# HTS221.net
KiCad netlist of a schematic drawn in Altium Designer
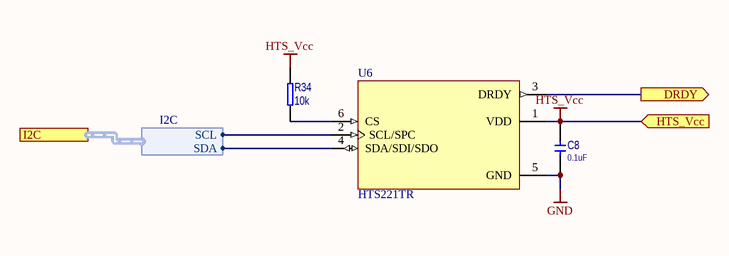
[diagram p0: HTS221.SchDoc]

(export (version "E")
  (design (tool "Eeschema 10.0.6"))
  (components
    (comp (ref "C8")
      (value "0.1uF")
      (footprint "CERCAP 0402")
      (description "Capacitor")
      (fields (field (name "Comment") "CERCAP 0402 0.1uF * X7R"))
      (libsource (lib "!main") (part "!Capacitor"))
    )
    (comp (ref "R34")
      (value "10k")
      (footprint "RES 0402")
      (description "Resistor")
      (fields (field (name "Comment") "RES 0402 10k"))
      (libsource (lib "!main") (part "!Resistor"))
    )
    (comp (ref "U6")
      (value "HTS221TR")
      (footprint "SI_PCBLIB_LGA:LGA6_HTS221")
      (description "Humidity Temperature Sensor 0 ~ 100% RH IÂ²C, SPI Â±4.5% RH 10s Surface Mount")
      (fields (field (name "MF") "STMicroelectronics") (field (name "DIGI-KEY_PART_NUMBER") "497-15382-1-ND"))
      (libsource (lib "SI_LIBSCH_Sensors") (part "HTS221TR"))
    )
  )
  (nets
    (net (code "2") (name "/DRDY") (class "Default")
      (node (ref "U6") (pin "3") (pinfunction "DRDY_3") (pintype "output"))
    )
    (net (code "3") (name "/SCL") (class "Default")
      (node (ref "U6") (pin "2") (pinfunction "SCL/SPC_2") (pintype "input"))
    )
    (net (code "4") (name "/SDA") (class "Default")
      (node (ref "U6") (pin "4") (pinfunction "SDA/SDI/SDO_4") (pintype "bidirectional"))
    )
    (net (code "6") (name "GND") (class "Default")
      (node (ref "C8") (pin "1") (pintype "passive"))
      (node (ref "U6") (pin "5") (pinfunction "GND_5") (pintype "power_in"))
    )
    (net (code "7") (name "HTS_Vcc") (class "Default")
      (node (ref "C8") (pin "2") (pintype "passive"))
      (node (ref "R34") (pin "2") (pinfunction "12_2") (pintype "passive"))
      (node (ref "U6") (pin "1") (pinfunction "VDD_1") (pintype "power_in"))
    )
    (net (code "8") (name "Net-(R34-11)") (class "Default")
      (node (ref "R34") (pin "1") (pinfunction "11_1") (pintype "passive"))
      (node (ref "U6") (pin "6") (pinfunction "CS_6") (pintype "input"))
    )
  )
)
